# Input.net
KiCad netlist of a schematic drawn in Altium Designer
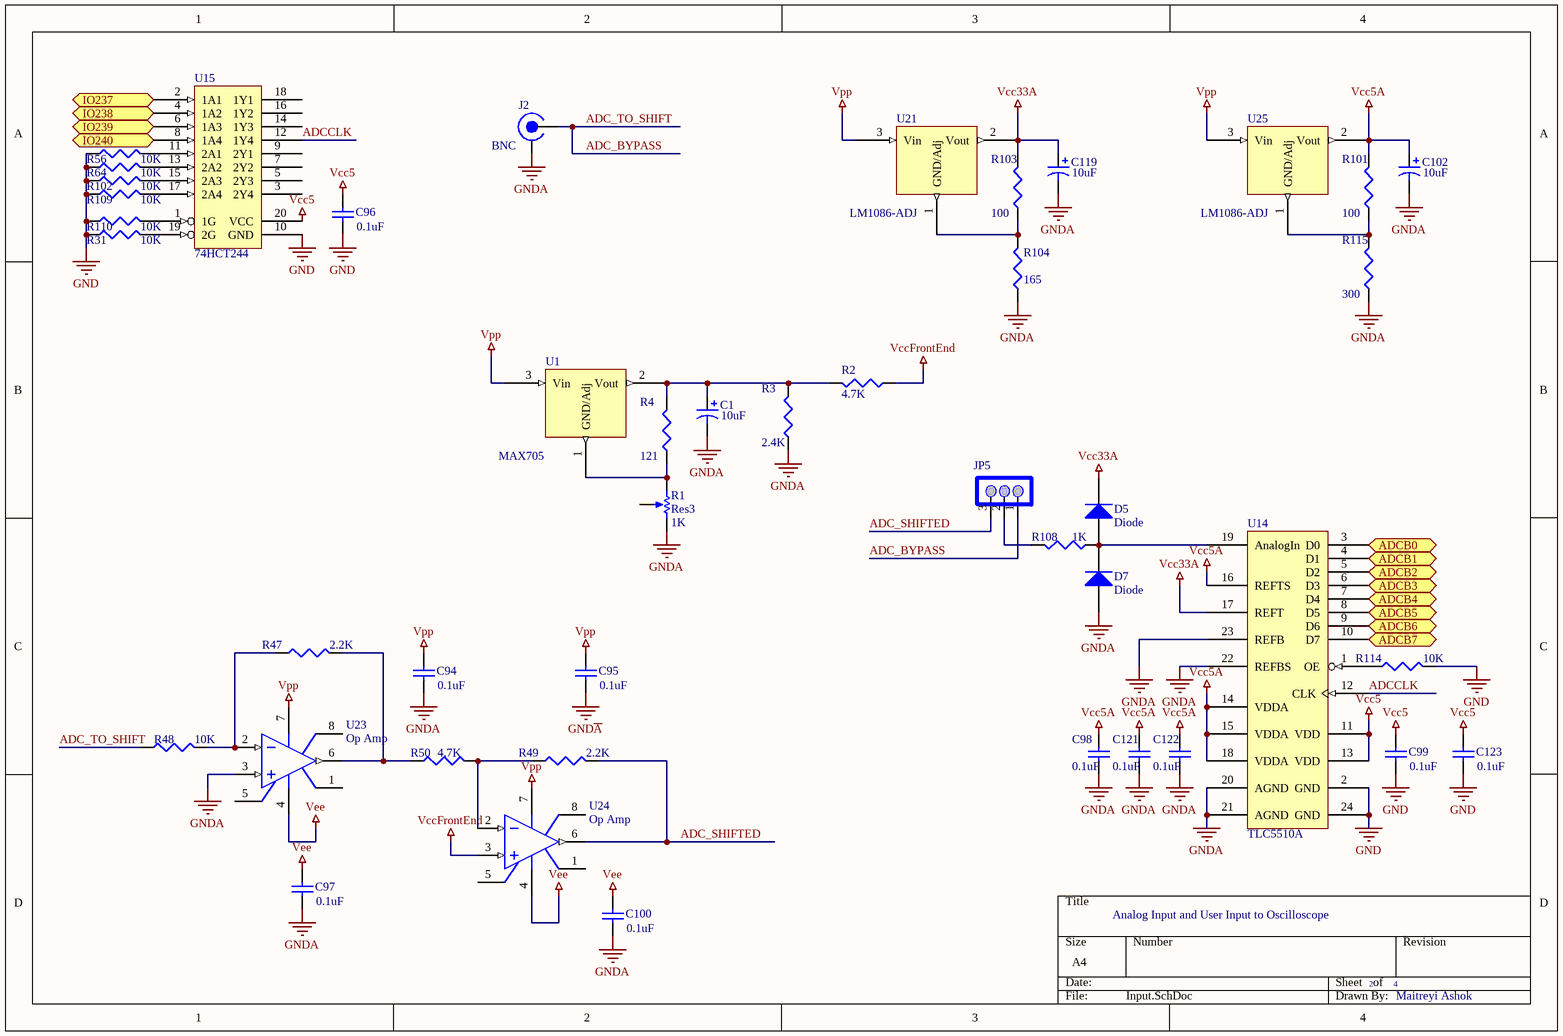
[diagram p0: Input.SchDoc]

(export (version "E")
  (design (tool "Eeschema 10.0.6"))
  (components
    (comp (ref "C1")
      (value "10uF")
      (footprint "1608[0603]")
      (description "Polarized Capacitor (Radial)")
      (fields (field (name "Comment") "Cap") (field (name "PUBLISHER") "Altium Limited"))
      (libsource (lib "Miscellaneous Devices") (part "Cap Pol1"))
    )
    (comp (ref "C94")
      (value "0.1uF")
      (footprint "1608[0603]")
      (description "Capacitor")
      (fields (field (name "Comment") "Cap") (field (name "PUBLISHER") "Altium Limited"))
      (libsource (lib "Miscellaneous Devices") (part "Cap"))
    )
    (comp (ref "C95")
      (value "0.1uF")
      (footprint "1608[0603]")
      (description "Capacitor")
      (fields (field (name "Comment") "Cap") (field (name "PUBLISHER") "Altium Limited"))
      (libsource (lib "Miscellaneous Devices") (part "Cap"))
    )
    (comp (ref "C96")
      (value "0.1uF")
      (footprint "1608[0603]")
      (description "Capacitor")
      (fields (field (name "Comment") "Cap") (field (name "PUBLISHER") "Altium Limited"))
      (libsource (lib "Miscellaneous Devices") (part "Cap"))
    )
    (comp (ref "C97")
      (value "0.1uF")
      (footprint "1608[0603]")
      (description "Capacitor")
      (fields (field (name "Comment") "Cap") (field (name "PUBLISHER") "Altium Limited"))
      (libsource (lib "Miscellaneous Devices") (part "Cap"))
    )
    (comp (ref "C98")
      (value "0.1uF")
      (footprint "1608[0603]")
      (description "Capacitor")
      (fields (field (name "Comment") "Cap") (field (name "PUBLISHER") "Altium Limited"))
      (libsource (lib "Miscellaneous Devices") (part "Cap"))
    )
    (comp (ref "C99")
      (value "0.1uF")
      (footprint "1608[0603]")
      (description "Capacitor")
      (fields (field (name "Comment") "Cap") (field (name "PUBLISHER") "Altium Limited"))
      (libsource (lib "Miscellaneous Devices") (part "Cap"))
    )
    (comp (ref "C100")
      (value "0.1uF")
      (footprint "1608[0603]")
      (description "Capacitor")
      (fields (field (name "Comment") "Cap") (field (name "PUBLISHER") "Altium Limited"))
      (libsource (lib "Miscellaneous Devices") (part "Cap"))
    )
    (comp (ref "C102")
      (value "10uF")
      (footprint "RB.1/.2")
      (description "Polarized Capacitor (Radial)")
      (fields (field (name "Comment") "Cap Pol1") (field (name "PUBLISHER") "Altium Limited"))
      (libsource (lib "Miscellaneous Devices") (part "Cap Pol1"))
    )
    (comp (ref "C119")
      (value "10uF")
      (footprint "RB.1/.2")
      (description "Polarized Capacitor (Radial)")
      (fields (field (name "Comment") "Cap Pol1") (field (name "PUBLISHER") "Altium Limited"))
      (libsource (lib "Miscellaneous Devices") (part "Cap Pol1"))
    )
    (comp (ref "C121")
      (value "0.1uF")
      (footprint "1608[0603]")
      (description "Capacitor")
      (fields (field (name "Comment") "Cap") (field (name "PUBLISHER") "Altium Limited"))
      (libsource (lib "Miscellaneous Devices") (part "Cap"))
    )
    (comp (ref "C122")
      (value "0.1uF")
      (footprint "1608[0603]")
      (description "Capacitor")
      (fields (field (name "Comment") "Cap") (field (name "PUBLISHER") "Altium Limited"))
      (libsource (lib "Miscellaneous Devices") (part "Cap"))
    )
    (comp (ref "C123")
      (value "0.1uF")
      (footprint "1608[0603]")
      (description "Capacitor")
      (fields (field (name "Comment") "Cap") (field (name "PUBLISHER") "Altium Limited"))
      (libsource (lib "Miscellaneous Devices") (part "Cap"))
    )
    (comp (ref "D5")
      (value "Diode")
      (footprint "SMB")
      (description "LSM115JE3/TR13")
      (fields (field (name "PUBLISHER") "Altium Limited"))
      (libsource (lib "Miscellaneous Devices") (part "Diode"))
    )
    (comp (ref "D7")
      (value "Diode")
      (footprint "SMB")
      (description "LSM115JE3/TR13")
      (fields (field (name "PUBLISHER") "Altium Limited"))
      (libsource (lib "Miscellaneous Devices") (part "Diode"))
    )
    (comp (ref "J2")
      (value "BNC")
      (footprint "AMP31-5540")
      (description "BNC Connector")
      (libsource (lib "eecs5x") (part "BNC"))
    )
    (comp (ref "JP5") (value "CLK01") (footprint "HDR1X3") (libsource (lib "*") (part "JUMPER3SM")))
    (comp (ref "R1")
      (value "Res3")
      (footprint "J1-0603")
      (description "Potentiometer")
      (fields (field (name "ALTIUM_VALUE") "1K") (field (name "PUBLISHER") "Altium Limited"))
      (libsource (lib "Miscellaneous Devices") (part "RPot"))
    )
    (comp (ref "R2")
      (value "4.7K")
      (footprint "J1-0603")
      (description "Resistor")
      (fields (field (name "Comment") "Res3") (field (name "PUBLISHER") "Altium Limited"))
      (libsource (lib "Miscellaneous Devices") (part "Res3"))
    )
    (comp (ref "R3")
      (value "2.4K")
      (footprint "J1-0603")
      (description "Resistor")
      (fields (field (name "Comment") "Res3") (field (name "PUBLISHER") "Altium Limited"))
      (libsource (lib "Miscellaneous Devices") (part "Res3"))
    )
    (comp (ref "R4")
      (value "121")
      (footprint "J1-0603")
      (description "Resistor")
      (fields (field (name "Comment") "Res3") (field (name "PUBLISHER") "Altium Limited"))
      (libsource (lib "Miscellaneous Devices") (part "Res3"))
    )
    (comp (ref "R31")
      (value "10K")
      (footprint "J1-0603")
      (description "Resistor")
      (fields (field (name "Comment") "Res3") (field (name "PUBLISHER") "Altium Limited"))
      (libsource (lib "Miscellaneous Devices") (part "Res3"))
    )
    (comp (ref "R47")
      (value "2.2K")
      (footprint "J1-0603")
      (description "Resistor")
      (fields (field (name "Comment") "551") (field (name "PUBLISHER") "Altium Limited"))
      (libsource (lib "Miscellaneous Devices") (part "Res3"))
    )
    (comp (ref "R48")
      (value "10K")
      (footprint "J1-0603")
      (description "Resistor")
      (fields (field (name "Comment") "551") (field (name "PUBLISHER") "Altium Limited"))
      (libsource (lib "Miscellaneous Devices") (part "Res3"))
    )
    (comp (ref "R49")
      (value "2.2K")
      (footprint "J1-0603")
      (description "Resistor")
      (fields (field (name "Comment") "551") (field (name "PUBLISHER") "Altium Limited"))
      (libsource (lib "Miscellaneous Devices") (part "Res3"))
    )
    (comp (ref "R50")
      (value "4.7K")
      (footprint "J1-0603")
      (description "Resistor")
      (fields (field (name "Comment") "551") (field (name "PUBLISHER") "Altium Limited"))
      (libsource (lib "Miscellaneous Devices") (part "Res3"))
    )
    (comp (ref "R56")
      (value "10K")
      (footprint "J1-0603")
      (description "Resistor")
      (fields (field (name "Comment") "Res3") (field (name "PUBLISHER") "Altium Limited"))
      (libsource (lib "Miscellaneous Devices") (part "Res3"))
    )
    (comp (ref "R64")
      (value "10K")
      (footprint "J1-0603")
      (description "Resistor")
      (fields (field (name "Comment") "Res3") (field (name "PUBLISHER") "Altium Limited"))
      (libsource (lib "Miscellaneous Devices") (part "Res3"))
    )
    (comp (ref "R101")
      (value "100")
      (footprint "J1-0603")
      (description "Resistor")
      (fields (field (name "Comment") "Res3") (field (name "PUBLISHER") "Altium Limited"))
      (libsource (lib "Miscellaneous Devices") (part "Res3"))
    )
    (comp (ref "R102")
      (value "10K")
      (footprint "J1-0603")
      (description "Resistor")
      (fields (field (name "Comment") "Res3") (field (name "PUBLISHER") "Altium Limited"))
      (libsource (lib "Miscellaneous Devices") (part "Res3"))
    )
    (comp (ref "R103")
      (value "100")
      (footprint "J1-0603")
      (description "Resistor")
      (fields (field (name "Comment") "Res3") (field (name "PUBLISHER") "Altium Limited"))
      (libsource (lib "Miscellaneous Devices") (part "Res3"))
    )
    (comp (ref "R104")
      (value "165")
      (footprint "J1-0603")
      (description "Resistor")
      (fields (field (name "Comment") "Res3") (field (name "PUBLISHER") "Altium Limited"))
      (libsource (lib "Miscellaneous Devices") (part "Res3"))
    )
    (comp (ref "R108")
      (value "1K")
      (footprint "J1-0603")
      (description "Resistor")
      (fields (field (name "Comment") "Res3") (field (name "PUBLISHER") "Altium Limited"))
      (libsource (lib "Miscellaneous Devices") (part "Res3"))
    )
    (comp (ref "R109")
      (value "10K")
      (footprint "J1-0603")
      (description "Resistor")
      (fields (field (name "Comment") "Res3") (field (name "PUBLISHER") "Altium Limited"))
      (libsource (lib "Miscellaneous Devices") (part "Res3"))
    )
    (comp (ref "R110")
      (value "10K")
      (footprint "J1-0603")
      (description "Resistor")
      (fields (field (name "Comment") "Res3") (field (name "PUBLISHER") "Altium Limited"))
      (libsource (lib "Miscellaneous Devices") (part "Res3"))
    )
    (comp (ref "R114")
      (value "10K")
      (footprint "J1-0603")
      (description "Resistor")
      (fields (field (name "Comment") "Res3") (field (name "PUBLISHER") "Altium Limited"))
      (libsource (lib "Miscellaneous Devices") (part "Res3"))
    )
    (comp (ref "R115")
      (value "300")
      (footprint "J1-0603")
      (description "Resistor")
      (fields (field (name "Comment") "Res3") (field (name "PUBLISHER") "Altium Limited"))
      (libsource (lib "Miscellaneous Devices") (part "Res3"))
    )
    (comp (ref "U1")
      (value "MAX705")
      (footprint "TO-220")
      (description "1.5A Low Dropout Positive Regulator")
      (libsource (lib "eecs5x") (part "LM1086"))
    )
    (comp (ref "U14")
      (value "TLC5510A")
      (footprint "TSSOP24")
      (description "TI 8-bit A/D Converter")
      (libsource (lib "eecs5x") (part "TLC5510A"))
    )
    (comp (ref "U15")
      (value "74HCT244")
      (footprint "DIPS20")
      (description "Octal Buffer")
      (libsource (lib "eecs5x") (part "74HCT244"))
    )
    (comp (ref "U21")
      (value "LM1086-ADJ")
      (footprint "TO-220V")
      (description "1.5A Low Dropout Positive Regulator")
      (libsource (lib "eecs5x") (part "LM1086"))
    )
    (comp (ref "U23")
      (value "Op Amp")
      (footprint "SO-8")
      (description "FET Operational Amplifier")
      (fields (field (name "PUBLISHER") "Altium Limited"))
      (libsource (lib "Miscellaneous Devices") (part "Op Amp"))
    )
    (comp (ref "U24")
      (value "Op Amp")
      (footprint "SO-8")
      (description "FET Operational Amplifier")
      (fields (field (name "PUBLISHER") "Altium Limited"))
      (libsource (lib "Miscellaneous Devices") (part "Op Amp"))
    )
    (comp (ref "U25")
      (value "LM1086-ADJ")
      (footprint "TO-220V")
      (description "1.5A Low Dropout Positive Regulator")
      (libsource (lib "eecs5x") (part "LM1086"))
    )
  )
  (nets
    (net (code "1") (name "/ADCB0") (class "Default")
      (node (ref "U14") (pin "3") (pinfunction "D0_3") (pintype "tri_state"))
    )
    (net (code "2") (name "/ADCB1") (class "Default")
      (node (ref "U14") (pin "4") (pinfunction "D1_4") (pintype "tri_state"))
    )
    (net (code "3") (name "/ADCB2") (class "Default")
      (node (ref "U14") (pin "5") (pinfunction "D2_5") (pintype "tri_state"))
    )
    (net (code "4") (name "/ADCB3") (class "Default")
      (node (ref "U14") (pin "6") (pinfunction "D3_6") (pintype "tri_state"))
    )
    (net (code "5") (name "/ADCB4") (class "Default")
      (node (ref "U14") (pin "7") (pinfunction "D4_7") (pintype "tri_state"))
    )
    (net (code "6") (name "/ADCB5") (class "Default")
      (node (ref "U14") (pin "8") (pinfunction "D5_8") (pintype "tri_state"))
    )
    (net (code "7") (name "/ADCB6") (class "Default")
      (node (ref "U14") (pin "9") (pinfunction "D6_9") (pintype "tri_state"))
    )
    (net (code "8") (name "/ADCB7") (class "Default")
      (node (ref "U14") (pin "10") (pinfunction "D7_10") (pintype "tri_state"))
    )
    (net (code "9") (name "/ADCCLK") (class "Default")
      (node (ref "U14") (pin "12") (pinfunction "CLK_12") (pintype "input"))
      (node (ref "U15") (pin "12") (pinfunction "1Y4_12") (pintype "tri_state"))
    )
    (net (code "10") (name "/ADC_BYPASS") (class "Default")
      (node (ref "J2") (pin "1") (pinfunction "SIGNAL_1") (pintype "passive"))
      (node (ref "JP5") (pin "1") (pinfunction "J1_1") (pintype "passive"))
      (node (ref "R48") (pin "1") (pinfunction "1_1") (pintype "passive"))
    )
    (net (code "11") (name "/ADC_SHIFTED") (class "Default")
      (node (ref "JP5") (pin "3") (pinfunction "J3_3") (pintype "passive"))
      (node (ref "R49") (pin "2") (pinfunction "2_2") (pintype "passive"))
      (node (ref "U24") (pin "6") (pinfunction "OUT_6") (pintype "output"))
    )
    (net (code "12") (name "/IO237") (class "Default")
      (node (ref "U15") (pin "2") (pinfunction "1A1_2") (pintype "input"))
    )
    (net (code "13") (name "/IO238") (class "Default")
      (node (ref "U15") (pin "4") (pinfunction "1A2_4") (pintype "input"))
    )
    (net (code "14") (name "/IO239") (class "Default")
      (node (ref "U15") (pin "6") (pinfunction "1A3_6") (pintype "input"))
    )
    (net (code "15") (name "/IO240") (class "Default")
      (node (ref "U15") (pin "8") (pinfunction "1A4_8") (pintype "input"))
    )
    (net (code "16") (name "GND") (class "Default")
      (node (ref "C123") (pin "1") (pinfunction "1_1") (pintype "passive"))
      (node (ref "C96") (pin "1") (pinfunction "1_1") (pintype "passive"))
      (node (ref "C99") (pin "1") (pinfunction "1_1") (pintype "passive"))
      (node (ref "R102") (pin "1") (pinfunction "1_1") (pintype "passive"))
      (node (ref "R109") (pin "1") (pinfunction "1_1") (pintype "passive"))
      (node (ref "R110") (pin "1") (pinfunction "1_1") (pintype "passive"))
      (node (ref "R114") (pin "2") (pinfunction "2_2") (pintype "passive"))
      (node (ref "R31") (pin "1") (pinfunction "1_1") (pintype "passive"))
      (node (ref "R56") (pin "1") (pinfunction "1_1") (pintype "passive"))
      (node (ref "R64") (pin "1") (pinfunction "1_1") (pintype "passive"))
      (node (ref "U14") (pin "2") (pinfunction "GND_2") (pintype "power_in"))
      (node (ref "U14") (pin "24") (pinfunction "GND_24") (pintype "power_in"))
      (node (ref "U15") (pin "10") (pinfunction "GND_10") (pintype "power_in"))
    )
    (net (code "17") (name "GNDA") (class "Default")
      (node (ref "C1") (pin "2") (pinfunction "2_2") (pintype "passive"))
      (node (ref "C100") (pin "1") (pinfunction "1_1") (pintype "passive"))
      (node (ref "C102") (pin "2") (pinfunction "2_2") (pintype "passive"))
      (node (ref "C119") (pin "2") (pinfunction "2_2") (pintype "passive"))
      (node (ref "C121") (pin "1") (pinfunction "1_1") (pintype "passive"))
      (node (ref "C122") (pin "1") (pinfunction "1_1") (pintype "passive"))
      (node (ref "C94") (pin "1") (pinfunction "1_1") (pintype "passive"))
      (node (ref "C97") (pin "1") (pinfunction "1_1") (pintype "passive"))
      (node (ref "C98") (pin "1") (pinfunction "1_1") (pintype "passive"))
      (node (ref "D7") (pin "1") (pinfunction "A_1") (pintype "passive"))
      (node (ref "J2") (pin "2") (pinfunction "SHIELD_2") (pintype "passive"))
      (node (ref "R1") (pin "2") (pinfunction "BOT_2") (pintype "passive"))
      (node (ref "R104") (pin "1") (pinfunction "1_1") (pintype "passive"))
      (node (ref "R115") (pin "1") (pinfunction "1_1") (pintype "passive"))
      (node (ref "R3") (pin "1") (pinfunction "1_1") (pintype "passive"))
      (node (ref "U14") (pin "20") (pinfunction "AGND_20") (pintype "power_in"))
      (node (ref "U14") (pin "21") (pinfunction "AGND_21") (pintype "power_in"))
      (node (ref "U14") (pin "22") (pinfunction "REFBS_22") (pintype "passive"))
      (node (ref "U14") (pin "23") (pinfunction "REFB_23") (pintype "passive"))
      (node (ref "U23") (pin "3") (pinfunction "IN+_3") (pintype "input"))
    )
    (net (code "18") (name "GND~{A}") (class "Default")
      (node (ref "C95") (pin "1") (pinfunction "1_1") (pintype "passive"))
    )
    (net (code "19") (name "Net-(D5-A)") (class "Default")
      (node (ref "D5") (pin "1") (pinfunction "A_1") (pintype "passive"))
      (node (ref "D7") (pin "2") (pinfunction "K_2") (pintype "passive"))
      (node (ref "R108") (pin "1") (pinfunction "1_1") (pintype "passive"))
      (node (ref "U14") (pin "19") (pinfunction "AnalogIn_19") (pintype "passive"))
    )
    (net (code "20") (name "Net-(JP5-J2)") (class "Default")
      (node (ref "JP5") (pin "2") (pinfunction "J2_2") (pintype "passive"))
      (node (ref "R108") (pin "2") (pinfunction "2_2") (pintype "passive"))
    )
    (net (code "21") (name "Net-(R1-TOP)") (class "Default")
      (node (ref "R1") (pin "1") (pinfunction "TOP_1") (pintype "passive"))
      (node (ref "R4") (pin "1") (pinfunction "1_1") (pintype "passive"))
      (node (ref "U1") (pin "1") (pinfunction "GND/Adj_1") (pintype "output"))
    )
    (net (code "22") (name "Net-(U1-Vout)") (class "Default")
      (node (ref "C1") (pin "1") (pinfunction "1_1") (pintype "passive"))
      (node (ref "R2") (pin "2") (pinfunction "2_2") (pintype "passive"))
      (node (ref "R3") (pin "2") (pinfunction "2_2") (pintype "passive"))
      (node (ref "R4") (pin "2") (pinfunction "2_2") (pintype "passive"))
      (node (ref "U1") (pin "2") (pinfunction "Vout_2") (pintype "output"))
    )
    (net (code "23") (name "Net-(U14-OE)") (class "Default")
      (node (ref "R114") (pin "1") (pinfunction "1_1") (pintype "passive"))
      (node (ref "U14") (pin "1") (pinfunction "OE_1") (pintype "input"))
    )
    (net (code "24") (name "Net-(U15-1G)") (class "Default")
      (node (ref "R110") (pin "2") (pinfunction "2_2") (pintype "passive"))
      (node (ref "U15") (pin "1") (pinfunction "1G_1") (pintype "input"))
    )
    (net (code "25") (name "Net-(U15-2A1)") (class "Default")
      (node (ref "R56") (pin "2") (pinfunction "2_2") (pintype "passive"))
      (node (ref "U15") (pin "11") (pinfunction "2A1_11") (pintype "input"))
    )
    (net (code "26") (name "Net-(U15-2A2)") (class "Default")
      (node (ref "R64") (pin "2") (pinfunction "2_2") (pintype "passive"))
      (node (ref "U15") (pin "13") (pinfunction "2A2_13") (pintype "input"))
    )
    (net (code "27") (name "Net-(U15-2A3)") (class "Default")
      (node (ref "R102") (pin "2") (pinfunction "2_2") (pintype "passive"))
      (node (ref "U15") (pin "15") (pinfunction "2A3_15") (pintype "input"))
    )
    (net (code "28") (name "Net-(U15-2A4)") (class "Default")
      (node (ref "R109") (pin "2") (pinfunction "2_2") (pintype "passive"))
      (node (ref "U15") (pin "17") (pinfunction "2A4_17") (pintype "input"))
    )
    (net (code "29") (name "Net-(U15-2G)") (class "Default")
      (node (ref "R31") (pin "2") (pinfunction "2_2") (pintype "passive"))
      (node (ref "U15") (pin "19") (pinfunction "2G_19") (pintype "input"))
    )
    (net (code "30") (name "Net-(U21-GND{slash}Adj)") (class "Default")
      (node (ref "R103") (pin "1") (pinfunction "1_1") (pintype "passive"))
      (node (ref "R104") (pin "2") (pinfunction "2_2") (pintype "passive"))
      (node (ref "U21") (pin "1") (pinfunction "GND/Adj_1") (pintype "output"))
    )
    (net (code "31") (name "Net-(U23-IN-)") (class "Default")
      (node (ref "R47") (pin "1") (pinfunction "1_1") (pintype "passive"))
      (node (ref "R48") (pin "2") (pinfunction "2_2") (pintype "passive"))
      (node (ref "U23") (pin "2") (pinfunction "IN-_2") (pintype "input"))
    )
    (net (code "32") (name "Net-(U23-OUT)") (class "Default")
      (node (ref "R47") (pin "2") (pinfunction "2_2") (pintype "passive"))
      (node (ref "R50") (pin "1") (pinfunction "1_1") (pintype "passive"))
      (node (ref "U23") (pin "6") (pinfunction "OUT_6") (pintype "output"))
    )
    (net (code "33") (name "Net-(U24-IN-)") (class "Default")
      (node (ref "R49") (pin "1") (pinfunction "1_1") (pintype "passive"))
      (node (ref "R50") (pin "2") (pinfunction "2_2") (pintype "passive"))
      (node (ref "U24") (pin "2") (pinfunction "IN-_2") (pintype "input"))
    )
    (net (code "34") (name "Net-(U25-GND{slash}Adj)") (class "Default")
      (node (ref "R101") (pin "1") (pinfunction "1_1") (pintype "passive"))
      (node (ref "R115") (pin "2") (pinfunction "2_2") (pintype "passive"))
      (node (ref "U25") (pin "1") (pinfunction "GND/Adj_1") (pintype "output"))
    )
    (net (code "35") (name "Vcc5") (class "Default")
      (node (ref "C123") (pin "2") (pinfunction "2_2") (pintype "passive"))
      (node (ref "C96") (pin "2") (pinfunction "2_2") (pintype "passive"))
      (node (ref "C99") (pin "2") (pinfunction "2_2") (pintype "passive"))
      (node (ref "U14") (pin "11") (pinfunction "VDD_11") (pintype "power_in"))
      (node (ref "U14") (pin "13") (pinfunction "VDD_13") (pintype "power_in"))
      (node (ref "U15") (pin "20") (pinfunction "VCC_20") (pintype "power_in"))
    )
    (net (code "36") (name "Vcc5A") (class "Default")
      (node (ref "C102") (pin "1") (pinfunction "1_1") (pintype "passive"))
      (node (ref "C121") (pin "2") (pinfunction "2_2") (pintype "passive"))
      (node (ref "C122") (pin "2") (pinfunction "2_2") (pintype "passive"))
      (node (ref "C98") (pin "2") (pinfunction "2_2") (pintype "passive"))
      (node (ref "R101") (pin "2") (pinfunction "2_2") (pintype "passive"))
      (node (ref "U14") (pin "14") (pinfunction "VDDA_14") (pintype "power_in"))
      (node (ref "U14") (pin "15") (pinfunction "VDDA_15") (pintype "power_in"))
      (node (ref "U14") (pin "16") (pinfunction "REFTS_16") (pintype "passive"))
      (node (ref "U14") (pin "18") (pinfunction "VDDA_18") (pintype "power_in"))
      (node (ref "U25") (pin "2") (pinfunction "Vout_2") (pintype "output"))
    )
    (net (code "37") (name "Vcc33A") (class "Default")
      (node (ref "C119") (pin "1") (pinfunction "1_1") (pintype "passive"))
      (node (ref "D5") (pin "2") (pinfunction "K_2") (pintype "passive"))
      (node (ref "R103") (pin "2") (pinfunction "2_2") (pintype "passive"))
      (node (ref "U14") (pin "17") (pinfunction "REFT_17") (pintype "passive"))
      (node (ref "U21") (pin "2") (pinfunction "Vout_2") (pintype "output"))
    )
    (net (code "38") (name "VccFrontEnd") (class "Default")
      (node (ref "R2") (pin "1") (pinfunction "1_1") (pintype "passive"))
      (node (ref "U24") (pin "3") (pinfunction "IN+_3") (pintype "input"))
    )
    (net (code "39") (name "Vee") (class "Default")
      (node (ref "C100") (pin "2") (pinfunction "2_2") (pintype "passive"))
      (node (ref "C97") (pin "2") (pinfunction "2_2") (pintype "passive"))
      (node (ref "U23") (pin "4") (pinfunction "V-_4") (pintype "power_in"))
      (node (ref "U24") (pin "4") (pinfunction "V-_4") (pintype "power_in"))
    )
    (net (code "40") (name "Vpp") (class "Default")
      (node (ref "C94") (pin "2") (pinfunction "2_2") (pintype "passive"))
      (node (ref "C95") (pin "2") (pinfunction "2_2") (pintype "passive"))
      (node (ref "U1") (pin "3") (pinfunction "Vin_3") (pintype "input"))
      (node (ref "U21") (pin "3") (pinfunction "Vin_3") (pintype "input"))
      (node (ref "U23") (pin "7") (pinfunction "V+_7") (pintype "power_in"))
      (node (ref "U24") (pin "7") (pinfunction "V+_7") (pintype "power_in"))
      (node (ref "U25") (pin "3") (pinfunction "Vin_3") (pintype "input"))
    )
    (net (code "41") (name "unconnected-(R1-TAP-Pad3)") (class "Default")
      (node (ref "R1") (pin "3") (pinfunction "TAP_3") (pintype "passive"))
    )
    (net (code "42") (name "unconnected-(U15-1Y1-Pad18)") (class "Default")
      (node (ref "U15") (pin "18") (pinfunction "1Y1_18") (pintype "tri_state"))
    )
    (net (code "43") (name "unconnected-(U15-1Y2-Pad16)") (class "Default")
      (node (ref "U15") (pin "16") (pinfunction "1Y2_16") (pintype "tri_state"))
    )
    (net (code "44") (name "unconnected-(U15-1Y3-Pad14)") (class "Default")
      (node (ref "U15") (pin "14") (pinfunction "1Y3_14") (pintype "tri_state"))
    )
    (net (code "45") (name "unconnected-(U15-2Y1-Pad9)") (class "Default")
      (node (ref "U15") (pin "9") (pinfunction "2Y1_9") (pintype "tri_state"))
    )
    (net (code "46") (name "unconnected-(U15-2Y2-Pad7)") (class "Default")
      (node (ref "U15") (pin "7") (pinfunction "2Y2_7") (pintype "tri_state"))
    )
    (net (code "47") (name "unconnected-(U15-2Y3-Pad5)") (class "Default")
      (node (ref "U15") (pin "5") (pinfunction "2Y3_5") (pintype "tri_state"))
    )
    (net (code "48") (name "unconnected-(U15-2Y4-Pad3)") (class "Default")
      (node (ref "U15") (pin "3") (pinfunction "2Y4_3") (pintype "tri_state"))
    )
    (net (code "49") (name "unconnected-(U23-OS_NUL-Pad1)") (class "Default")
      (node (ref "U23") (pin "1") (pinfunction "OS_NUL_1") (pintype "passive"))
    )
    (net (code "50") (name "unconnected-(U23-OS_NUL-Pad5)") (class "Default")
      (node (ref "U23") (pin "5") (pinfunction "OS_NUL_5") (pintype "passive"))
    )
    (net (code "51") (name "unconnected-(U23-TAB-Pad8)") (class "Default")
      (node (ref "U23") (pin "8") (pinfunction "TAB_8") (pintype "passive"))
    )
    (net (code "52") (name "unconnected-(U24-OS_NUL-Pad1)") (class "Default")
      (node (ref "U24") (pin "1") (pinfunction "OS_NUL_1") (pintype "passive"))
    )
    (net (code "53") (name "unconnected-(U24-OS_NUL-Pad5)") (class "Default")
      (node (ref "U24") (pin "5") (pinfunction "OS_NUL_5") (pintype "passive"))
    )
    (net (code "54") (name "unconnected-(U24-TAB-Pad8)") (class "Default")
      (node (ref "U24") (pin "8") (pinfunction "TAB_8") (pintype "passive"))
    )
  )
)
